# pca9535bo.net
KiCad netlist of a schematic drawn in EAGLE
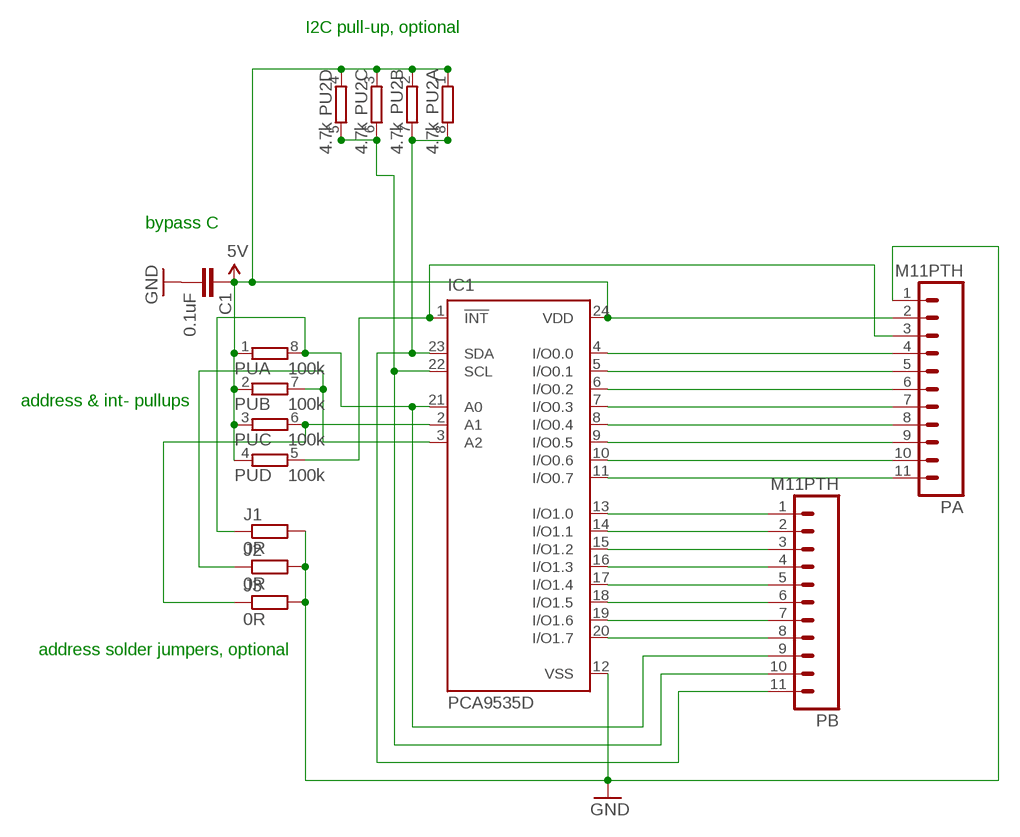
[diagram p0: schematic, sheet 1]

(export (version "E")
  (design (tool "Eeschema 10.0.6"))
  (components
    (comp (ref "C1")
      (value "0.1uF")
      (footprint "eagle-import:C0805K")
      (libsource (lib "eagle-import") (part "C-EUC0805K"))
    )
    (comp (ref "IC1")
      (value "PCA9535D")
      (footprint "eagle-import:SO24")
      (fields (field (name "MPN") "PCA9555DW"))
      (libsource (lib "eagle-import") (part "PCA9555D"))
    )
    (comp (ref "J1")
      (value "0R")
      (footprint "eagle-import:R0603")
      (libsource (lib "eagle-import") (part "R-EU_R0603"))
    )
    (comp (ref "J2")
      (value "0R")
      (footprint "eagle-import:R0603")
      (libsource (lib "eagle-import") (part "R-EU_R0603"))
    )
    (comp (ref "J3")
      (value "0R")
      (footprint "eagle-import:R0603")
      (libsource (lib "eagle-import") (part "R-EU_R0603"))
    )
    (comp (ref "PA")
      (value "M11PTH")
      (footprint "eagle-import:1X11")
      (libsource (lib "eagle-import") (part "M11PTH"))
    )
    (comp (ref "PB")
      (value "M11PTH")
      (footprint "eagle-import:1X11")
      (libsource (lib "eagle-import") (part "M11PTH"))
    )
    (comp (ref "PU")
      (value "100k")
      (footprint "eagle-import:CAY16")
      (libsource (lib "eagle-import") (part "4R-NCAY16"))
    )
    (comp (ref "PU2")
      (value "4.7k")
      (footprint "eagle-import:CAY16")
      (libsource (lib "eagle-import") (part "4R-NCAY16"))
    )
  )
  (nets
    (net (code "1") (name "5V") (class "Default")
      (node (ref "C1") (pin "1") (pinfunction "1_1") (pintype "passive"))
      (node (ref "IC1") (pin "24") (pinfunction "VDD_24") (pintype "power_in"))
      (node (ref "PA") (pin "2") (pinfunction "2_2") (pintype "passive"))
      (node (ref "PU") (pin "1") (pinfunction "1_1") (pintype "passive"))
      (node (ref "PU") (pin "2") (pinfunction "1_2") (pintype "passive"))
      (node (ref "PU") (pin "3") (pinfunction "1_3") (pintype "passive"))
      (node (ref "PU") (pin "4") (pinfunction "1_4") (pintype "passive"))
      (node (ref "PU2") (pin "1") (pinfunction "1_1") (pintype "passive"))
      (node (ref "PU2") (pin "2") (pinfunction "1_2") (pintype "passive"))
      (node (ref "PU2") (pin "3") (pinfunction "1_3") (pintype "passive"))
      (node (ref "PU2") (pin "4") (pinfunction "1_4") (pintype "passive"))
    )
    (net (code "2") (name "GND") (class "Default")
      (node (ref "C1") (pin "2") (pinfunction "2_2") (pintype "passive"))
      (node (ref "IC1") (pin "12") (pinfunction "VSS_12") (pintype "power_in"))
      (node (ref "J1") (pin "2") (pinfunction "2_2") (pintype "passive"))
      (node (ref "J2") (pin "2") (pinfunction "2_2") (pintype "passive"))
      (node (ref "J3") (pin "2") (pinfunction "2_2") (pintype "passive"))
      (node (ref "PA") (pin "1") (pinfunction "1_1") (pintype "passive"))
    )
    (net (code "3") (name "Net-(IC1-A0)") (class "Default")
      (node (ref "IC1") (pin "21") (pinfunction "A0_21") (pintype "input"))
      (node (ref "J1") (pin "1") (pinfunction "1_1") (pintype "passive"))
      (node (ref "PB") (pin "9") (pinfunction "9_9") (pintype "passive"))
      (node (ref "PU") (pin "8") (pinfunction "2_8") (pintype "passive"))
    )
    (net (code "4") (name "Net-(IC1-A1)") (class "Default")
      (node (ref "IC1") (pin "2") (pinfunction "A1_2") (pintype "input"))
      (node (ref "J3") (pin "1") (pinfunction "1_1") (pintype "passive"))
      (node (ref "PU") (pin "6") (pinfunction "2_6") (pintype "passive"))
    )
    (net (code "5") (name "Net-(IC1-A2)") (class "Default")
      (node (ref "IC1") (pin "3") (pinfunction "A2_3") (pintype "input"))
      (node (ref "J2") (pin "1") (pinfunction "1_1") (pintype "passive"))
      (node (ref "PU") (pin "7") (pinfunction "2_7") (pintype "passive"))
    )
    (net (code "6") (name "Net-(IC1-I{slash}O0.0)") (class "Default")
      (node (ref "IC1") (pin "4") (pinfunction "I/O0.0_4") (pintype "bidirectional"))
      (node (ref "PA") (pin "4") (pinfunction "4_4") (pintype "passive"))
    )
    (net (code "7") (name "Net-(IC1-I{slash}O0.1)") (class "Default")
      (node (ref "IC1") (pin "5") (pinfunction "I/O0.1_5") (pintype "bidirectional"))
      (node (ref "PA") (pin "5") (pinfunction "5_5") (pintype "passive"))
    )
    (net (code "8") (name "Net-(IC1-I{slash}O0.2)") (class "Default")
      (node (ref "IC1") (pin "6") (pinfunction "I/O0.2_6") (pintype "bidirectional"))
      (node (ref "PA") (pin "6") (pinfunction "6_6") (pintype "passive"))
    )
    (net (code "9") (name "Net-(IC1-I{slash}O0.3)") (class "Default")
      (node (ref "IC1") (pin "7") (pinfunction "I/O0.3_7") (pintype "bidirectional"))
      (node (ref "PA") (pin "7") (pinfunction "7_7") (pintype "passive"))
    )
    (net (code "10") (name "Net-(IC1-I{slash}O0.4)") (class "Default")
      (node (ref "IC1") (pin "8") (pinfunction "I/O0.4_8") (pintype "bidirectional"))
      (node (ref "PA") (pin "8") (pinfunction "8_8") (pintype "passive"))
    )
    (net (code "11") (name "Net-(IC1-I{slash}O0.5)") (class "Default")
      (node (ref "IC1") (pin "9") (pinfunction "I/O0.5_9") (pintype "bidirectional"))
      (node (ref "PA") (pin "9") (pinfunction "9_9") (pintype "passive"))
    )
    (net (code "12") (name "Net-(IC1-I{slash}O0.6)") (class "Default")
      (node (ref "IC1") (pin "10") (pinfunction "I/O0.6_10") (pintype "bidirectional"))
      (node (ref "PA") (pin "10") (pinfunction "10_10") (pintype "passive"))
    )
    (net (code "13") (name "Net-(IC1-I{slash}O0.7)") (class "Default")
      (node (ref "IC1") (pin "11") (pinfunction "I/O0.7_11") (pintype "bidirectional"))
      (node (ref "PA") (pin "11") (pinfunction "11_11") (pintype "passive"))
    )
    (net (code "14") (name "Net-(IC1-I{slash}O1.0)") (class "Default")
      (node (ref "IC1") (pin "13") (pinfunction "I/O1.0_13") (pintype "bidirectional"))
      (node (ref "PB") (pin "1") (pinfunction "1_1") (pintype "passive"))
    )
    (net (code "15") (name "Net-(IC1-I{slash}O1.1)") (class "Default")
      (node (ref "IC1") (pin "14") (pinfunction "I/O1.1_14") (pintype "bidirectional"))
      (node (ref "PB") (pin "2") (pinfunction "2_2") (pintype "passive"))
    )
    (net (code "16") (name "Net-(IC1-I{slash}O1.2)") (class "Default")
      (node (ref "IC1") (pin "15") (pinfunction "I/O1.2_15") (pintype "bidirectional"))
      (node (ref "PB") (pin "3") (pinfunction "3_3") (pintype "passive"))
    )
    (net (code "17") (name "Net-(IC1-I{slash}O1.3)") (class "Default")
      (node (ref "IC1") (pin "16") (pinfunction "I/O1.3_16") (pintype "bidirectional"))
      (node (ref "PB") (pin "4") (pinfunction "4_4") (pintype "passive"))
    )
    (net (code "18") (name "Net-(IC1-I{slash}O1.4)") (class "Default")
      (node (ref "IC1") (pin "17") (pinfunction "I/O1.4_17") (pintype "bidirectional"))
      (node (ref "PB") (pin "5") (pinfunction "5_5") (pintype "passive"))
    )
    (net (code "19") (name "Net-(IC1-I{slash}O1.5)") (class "Default")
      (node (ref "IC1") (pin "18") (pinfunction "I/O1.5_18") (pintype "bidirectional"))
      (node (ref "PB") (pin "6") (pinfunction "6_6") (pintype "passive"))
    )
    (net (code "20") (name "Net-(IC1-I{slash}O1.6)") (class "Default")
      (node (ref "IC1") (pin "19") (pinfunction "I/O1.6_19") (pintype "bidirectional"))
      (node (ref "PB") (pin "7") (pinfunction "7_7") (pintype "passive"))
    )
    (net (code "21") (name "Net-(IC1-I{slash}O1.7)") (class "Default")
      (node (ref "IC1") (pin "20") (pinfunction "I/O1.7_20") (pintype "bidirectional"))
      (node (ref "PB") (pin "8") (pinfunction "8_8") (pintype "passive"))
    )
    (net (code "22") (name "Net-(IC1-SCL)") (class "Default")
      (node (ref "IC1") (pin "22") (pinfunction "SCL_22") (pintype "input"))
      (node (ref "PB") (pin "10") (pinfunction "10_10") (pintype "passive"))
      (node (ref "PU2") (pin "5") (pinfunction "2_5") (pintype "passive"))
      (node (ref "PU2") (pin "6") (pinfunction "2_6") (pintype "passive"))
    )
    (net (code "23") (name "Net-(IC1-SDA)") (class "Default")
      (node (ref "IC1") (pin "23") (pinfunction "SDA_23") (pintype "bidirectional"))
      (node (ref "PB") (pin "11") (pinfunction "11_11") (pintype "passive"))
      (node (ref "PU2") (pin "7") (pinfunction "2_7") (pintype "passive"))
      (node (ref "PU2") (pin "8") (pinfunction "2_8") (pintype "passive"))
    )
    (net (code "24") (name "Net-(IC1-~{INT})") (class "Default")
      (node (ref "IC1") (pin "1") (pinfunction "~{INT}_1") (pintype "output"))
      (node (ref "PA") (pin "3") (pinfunction "3_3") (pintype "passive"))
      (node (ref "PU") (pin "5") (pinfunction "2_5") (pintype "passive"))
    )
  )
)
